# USB.net
KiCad netlist of a schematic drawn in Altium Designer
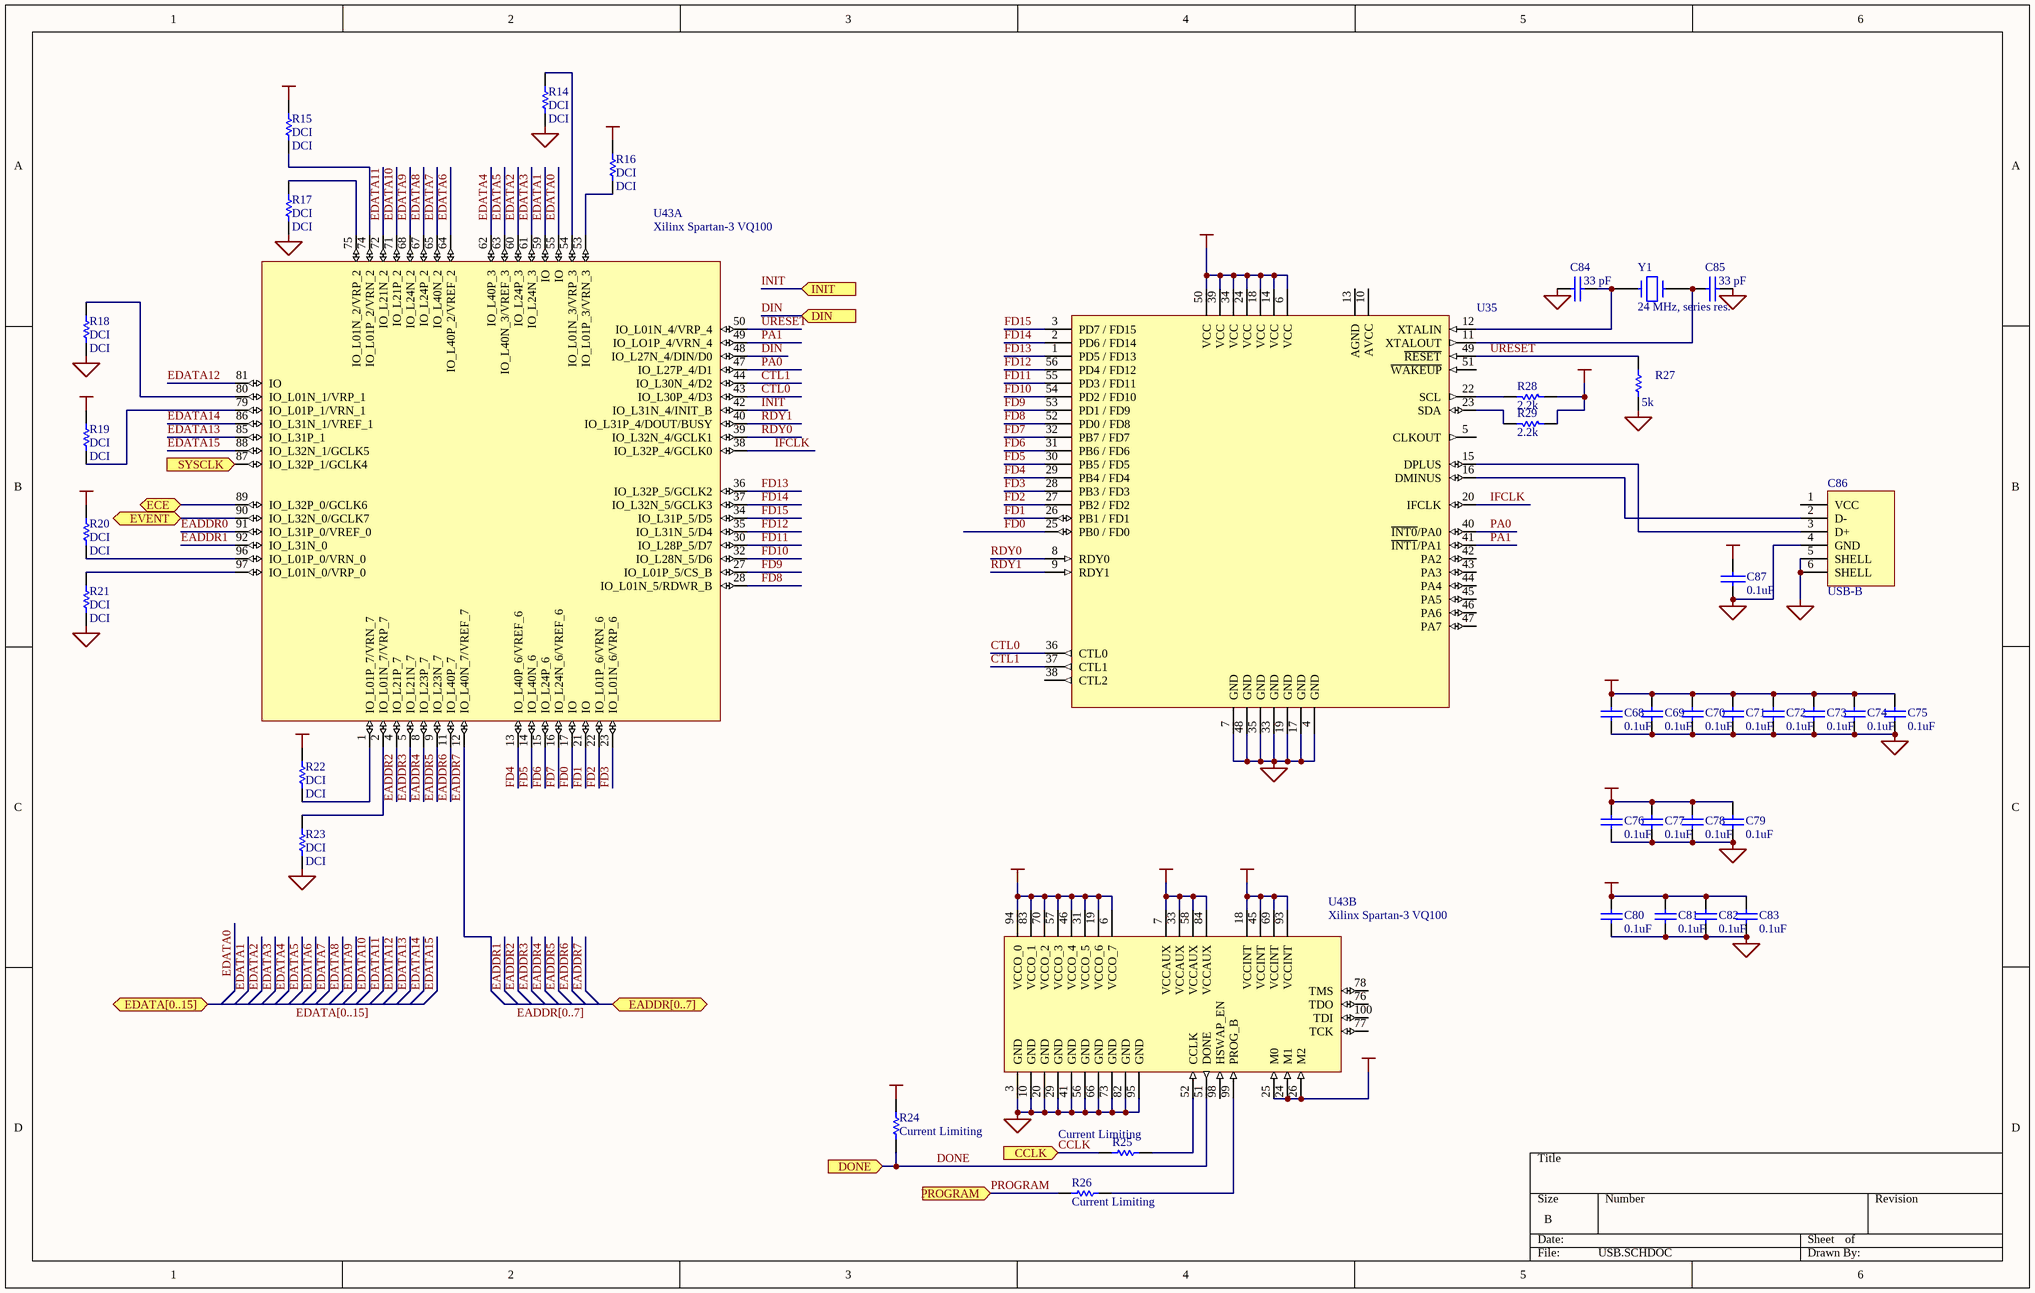
[diagram p0: USB.SCHDOC]

(export (version "E")
  (design (tool "Eeschema 10.0.6"))
  (components
    (comp (ref "C68")
      (value "0.1uF")
      (footprint "CC1608-0603")
      (description "Capacitor")
      (fields
        (field (name "MANUFACTURER") "Generic Components")
        (field (name "Comment") "Cap")
        (field (name "PUBLISHER") "Altium Limited")
      )
      (libsource (lib "Miscellaneous Devices") (part "Cap"))
    )
    (comp (ref "C69")
      (value "0.1uF")
      (footprint "CC1608-0603")
      (description "Capacitor")
      (fields
        (field (name "MANUFACTURER") "Generic Components")
        (field (name "Comment") "Cap")
        (field (name "PUBLISHER") "Altium Limited")
      )
      (libsource (lib "Miscellaneous Devices") (part "Cap"))
    )
    (comp (ref "C70")
      (value "0.1uF")
      (footprint "CC1608-0603")
      (description "Capacitor")
      (fields
        (field (name "MANUFACTURER") "Generic Components")
        (field (name "Comment") "Cap")
        (field (name "PUBLISHER") "Altium Limited")
      )
      (libsource (lib "Miscellaneous Devices") (part "Cap"))
    )
    (comp (ref "C71")
      (value "0.1uF")
      (footprint "CC1608-0603")
      (description "Capacitor")
      (fields
        (field (name "MANUFACTURER") "Generic Components")
        (field (name "Comment") "Cap")
        (field (name "PUBLISHER") "Altium Limited")
      )
      (libsource (lib "Miscellaneous Devices") (part "Cap"))
    )
    (comp (ref "C72")
      (value "0.1uF")
      (footprint "CC1608-0603")
      (description "Capacitor")
      (fields
        (field (name "MANUFACTURER") "Generic Components")
        (field (name "Comment") "Cap")
        (field (name "PUBLISHER") "Altium Limited")
      )
      (libsource (lib "Miscellaneous Devices") (part "Cap"))
    )
    (comp (ref "C73")
      (value "0.1uF")
      (footprint "CC1608-0603")
      (description "Capacitor")
      (fields
        (field (name "MANUFACTURER") "Generic Components")
        (field (name "Comment") "Cap")
        (field (name "PUBLISHER") "Altium Limited")
      )
      (libsource (lib "Miscellaneous Devices") (part "Cap"))
    )
    (comp (ref "C74")
      (value "0.1uF")
      (footprint "CC1608-0603")
      (description "Capacitor")
      (fields
        (field (name "MANUFACTURER") "Generic Components")
        (field (name "Comment") "Cap")
        (field (name "PUBLISHER") "Altium Limited")
      )
      (libsource (lib "Miscellaneous Devices") (part "Cap"))
    )
    (comp (ref "C75")
      (value "0.1uF")
      (footprint "CC1608-0603")
      (description "Capacitor")
      (fields
        (field (name "MANUFACTURER") "Generic Components")
        (field (name "Comment") "Cap")
        (field (name "PUBLISHER") "Altium Limited")
      )
      (libsource (lib "Miscellaneous Devices") (part "Cap"))
    )
    (comp (ref "C76")
      (value "0.1uF")
      (footprint "CC1608-0603")
      (description "Capacitor")
      (fields
        (field (name "MANUFACTURER") "Generic Components")
        (field (name "Comment") "Cap")
        (field (name "PUBLISHER") "Altium Limited")
      )
      (libsource (lib "Miscellaneous Devices") (part "Cap"))
    )
    (comp (ref "C77")
      (value "0.1uF")
      (footprint "CC1608-0603")
      (description "Capacitor")
      (fields
        (field (name "MANUFACTURER") "Generic Components")
        (field (name "Comment") "Cap")
        (field (name "PUBLISHER") "Altium Limited")
      )
      (libsource (lib "Miscellaneous Devices") (part "Cap"))
    )
    (comp (ref "C78")
      (value "0.1uF")
      (footprint "CC1608-0603")
      (description "Capacitor")
      (fields
        (field (name "MANUFACTURER") "Generic Components")
        (field (name "Comment") "Cap")
        (field (name "PUBLISHER") "Altium Limited")
      )
      (libsource (lib "Miscellaneous Devices") (part "Cap"))
    )
    (comp (ref "C79")
      (value "0.1uF")
      (footprint "CC1608-0603")
      (description "Capacitor")
      (fields
        (field (name "MANUFACTURER") "Generic Components")
        (field (name "Comment") "Cap")
        (field (name "PUBLISHER") "Altium Limited")
      )
      (libsource (lib "Miscellaneous Devices") (part "Cap"))
    )
    (comp (ref "C80")
      (value "0.1uF")
      (footprint "CC1608-0603")
      (description "Capacitor")
      (fields
        (field (name "MANUFACTURER") "Generic Components")
        (field (name "Comment") "Cap")
        (field (name "PUBLISHER") "Altium Limited")
      )
      (libsource (lib "Miscellaneous Devices") (part "Cap"))
    )
    (comp (ref "C81")
      (value "0.1uF")
      (footprint "CC1608-0603")
      (description "Capacitor")
      (fields
        (field (name "MANUFACTURER") "Generic Components")
        (field (name "Comment") "Cap")
        (field (name "PUBLISHER") "Altium Limited")
      )
      (libsource (lib "Miscellaneous Devices") (part "Cap"))
    )
    (comp (ref "C82")
      (value "0.1uF")
      (footprint "CC1608-0603")
      (description "Capacitor")
      (fields
        (field (name "MANUFACTURER") "Generic Components")
        (field (name "Comment") "Cap")
        (field (name "PUBLISHER") "Altium Limited")
      )
      (libsource (lib "Miscellaneous Devices") (part "Cap"))
    )
    (comp (ref "C83")
      (value "0.1uF")
      (footprint "CC1608-0603")
      (description "Capacitor")
      (fields
        (field (name "MANUFACTURER") "Generic Components")
        (field (name "Comment") "Cap")
        (field (name "PUBLISHER") "Altium Limited")
      )
      (libsource (lib "Miscellaneous Devices") (part "Cap"))
    )
    (comp (ref "C84")
      (value "33 pF")
      (footprint "CC1608-0603")
      (description "Capacitor")
      (libsource (lib "*") (part "CAP"))
    )
    (comp (ref "C85")
      (value "33 pF")
      (footprint "CC1608-0603")
      (description "Capacitor")
      (libsource (lib "*") (part "CAP"))
    )
    (comp (ref "C86") (value "USB-B") (footprint "USB-B") (libsource (lib "*") (part "USB-B")))
    (comp (ref "C87")
      (value "0.1uF")
      (footprint "CC1608-0603")
      (description "Capacitor")
      (libsource (lib "*") (part "CAP"))
    )
    (comp (ref "R14")
      (value "DCI")
      (footprint "CC1608-0603")
      (description "Resistor")
      (fields
        (field (name "MANUFACTURER") "Generic Components")
        (field (name "ALTIUM_VALUE") "DCI")
        (field (name "PUBLISHER") "Altium Limited")
      )
      (libsource (lib "Miscellaneous Devices") (part "Res1"))
    )
    (comp (ref "R15")
      (value "DCI")
      (footprint "CC1608-0603")
      (description "Resistor")
      (fields
        (field (name "MANUFACTURER") "Generic Components")
        (field (name "ALTIUM_VALUE") "DCI")
        (field (name "PUBLISHER") "Altium Limited")
      )
      (libsource (lib "Miscellaneous Devices") (part "Res1"))
    )
    (comp (ref "R16")
      (value "DCI")
      (footprint "CC1608-0603")
      (description "Resistor")
      (fields
        (field (name "MANUFACTURER") "Generic Components")
        (field (name "ALTIUM_VALUE") "DCI")
        (field (name "PUBLISHER") "Altium Limited")
      )
      (libsource (lib "Miscellaneous Devices") (part "Res1"))
    )
    (comp (ref "R17")
      (value "DCI")
      (footprint "CC1608-0603")
      (description "Resistor")
      (fields
        (field (name "MANUFACTURER") "Generic Components")
        (field (name "ALTIUM_VALUE") "DCI")
        (field (name "PUBLISHER") "Altium Limited")
      )
      (libsource (lib "Miscellaneous Devices") (part "Res1"))
    )
    (comp (ref "R18")
      (value "DCI")
      (footprint "CC1608-0603")
      (description "Resistor")
      (fields
        (field (name "MANUFACTURER") "Generic Components")
        (field (name "ALTIUM_VALUE") "DCI")
        (field (name "PUBLISHER") "Altium Limited")
      )
      (libsource (lib "Miscellaneous Devices") (part "Res1"))
    )
    (comp (ref "R19")
      (value "DCI")
      (footprint "CC1608-0603")
      (description "Resistor")
      (fields
        (field (name "MANUFACTURER") "Generic Components")
        (field (name "ALTIUM_VALUE") "DCI")
        (field (name "PUBLISHER") "Altium Limited")
      )
      (libsource (lib "Miscellaneous Devices") (part "Res1"))
    )
    (comp (ref "R20")
      (value "DCI")
      (footprint "CC1608-0603")
      (description "Resistor")
      (fields
        (field (name "MANUFACTURER") "Generic Components")
        (field (name "ALTIUM_VALUE") "DCI")
        (field (name "PUBLISHER") "Altium Limited")
      )
      (libsource (lib "Miscellaneous Devices") (part "Res1"))
    )
    (comp (ref "R21")
      (value "DCI")
      (footprint "CC1608-0603")
      (description "Resistor")
      (fields
        (field (name "MANUFACTURER") "Generic Components")
        (field (name "ALTIUM_VALUE") "DCI")
        (field (name "PUBLISHER") "Altium Limited")
      )
      (libsource (lib "Miscellaneous Devices") (part "Res1"))
    )
    (comp (ref "R22")
      (value "DCI")
      (footprint "CC1608-0603")
      (description "Resistor")
      (fields
        (field (name "MANUFACTURER") "Generic Components")
        (field (name "ALTIUM_VALUE") "DCI")
        (field (name "PUBLISHER") "Altium Limited")
      )
      (libsource (lib "Miscellaneous Devices") (part "Res1"))
    )
    (comp (ref "R23")
      (value "DCI")
      (footprint "CC1608-0603")
      (description "Resistor")
      (fields
        (field (name "MANUFACTURER") "Generic Components")
        (field (name "ALTIUM_VALUE") "DCI")
        (field (name "PUBLISHER") "Altium Limited")
      )
      (libsource (lib "Miscellaneous Devices") (part "Res1"))
    )
    (comp (ref "R24")
      (value "Current Limiting")
      (footprint "CC1608-0603")
      (description "Resistor")
      (fields (field (name "MANUFACTURER") "Generic Components") (field (name "PUBLISHER") "Altium Limited"))
      (libsource (lib "Miscellaneous Devices") (part "Res1"))
    )
    (comp (ref "R25")
      (value "Current Limiting")
      (footprint "CC1608-0603")
      (description "Resistor")
      (fields (field (name "MANUFACTURER") "Generic Components") (field (name "PUBLISHER") "Altium Limited"))
      (libsource (lib "Miscellaneous Devices") (part "Res1"))
    )
    (comp (ref "R26")
      (value "Current Limiting")
      (footprint "CC1608-0603")
      (description "Resistor")
      (fields (field (name "MANUFACTURER") "Generic Components") (field (name "PUBLISHER") "Altium Limited"))
      (libsource (lib "Miscellaneous Devices") (part "Res1"))
    )
    (comp (ref "R27")
      (value "5k")
      (footprint "CC3216-1206")
      (description "Resistor")
      (fields
        (field (name "MANUFACTURER") "Generic Components")
        (field (name "Comment") "Res1")
        (field (name "PUBLISHER") "Altium Limited")
      )
      (libsource (lib "Miscellaneous Devices") (part "Res1"))
    )
    (comp (ref "R28")
      (value "2.2k")
      (footprint "CC3216-1206")
      (description "Resistor")
      (fields
        (field (name "MANUFACTURER") "Generic Components")
        (field (name "Comment") "Res1")
        (field (name "PUBLISHER") "Altium Limited")
      )
      (libsource (lib "Miscellaneous Devices") (part "Res1"))
    )
    (comp (ref "R29")
      (value "2.2k")
      (footprint "CC3216-1206")
      (description "Resistor")
      (fields
        (field (name "MANUFACTURER") "Generic Components")
        (field (name "Comment") "Res1")
        (field (name "PUBLISHER") "Altium Limited")
      )
      (libsource (lib "Miscellaneous Devices") (part "Res1"))
    )
    (comp (ref "U35")
      (value "~")
      (footprint "SOP56FX2")
      (description "Cypress EZ-USB FX2")
      (libsource (lib "My devices") (part "CY7C68013-56"))
    )
    (comp (ref "U43")
      (value "Xilinx Spartan-3 VQ100")
      (footprint "F-QFP14X14-G100/N")
      (libsource (lib "My devices") (part "XC3S50-VQ100"))
    )
    (comp (ref "Y1")
      (value "24 MHz, series res.")
      (footprint "ECX-3S")
      (description "Crystal")
      (libsource (lib "*") (part "CRYSTAL"))
    )
  )
  (nets
    (net (code "1") (name "+1.2VCCUSB") (class "Default")
      (node (ref "C76") (pin "1") (pinfunction "1_1") (pintype "passive"))
      (node (ref "C77") (pin "1") (pinfunction "1_1") (pintype "passive"))
      (node (ref "C78") (pin "1") (pinfunction "1_1") (pintype "passive"))
      (node (ref "C79") (pin "1") (pinfunction "1_1") (pintype "passive"))
      (node (ref "U43") (pin "18") (pinfunction "VCCINT_18") (pintype "power_in"))
      (node (ref "U43") (pin "45") (pinfunction "VCCINT_45") (pintype "power_in"))
      (node (ref "U43") (pin "69") (pinfunction "VCCINT_69") (pintype "power_in"))
      (node (ref "U43") (pin "93") (pinfunction "VCCINT_93") (pintype "power_in"))
    )
    (net (code "2") (name "+2.5VCC") (class "Default")
      (node (ref "C80") (pin "1") (pinfunction "1_1") (pintype "passive"))
      (node (ref "C81") (pin "1") (pinfunction "1_1") (pintype "passive"))
      (node (ref "C82") (pin "1") (pinfunction "1_1") (pintype "passive"))
      (node (ref "C83") (pin "1") (pinfunction "1_1") (pintype "passive"))
      (node (ref "U43") (pin "33") (pinfunction "VCCAUX_33") (pintype "power_in"))
      (node (ref "U43") (pin "58") (pinfunction "VCCAUX_58") (pintype "power_in"))
      (node (ref "U43") (pin "7") (pinfunction "VCCAUX_7") (pintype "power_in"))
      (node (ref "U43") (pin "84") (pinfunction "VCCAUX_84") (pintype "power_in"))
    )
    (net (code "3") (name "/CCLK") (class "Default")
      (node (ref "R25") (pin "1") (pinfunction "1_1") (pintype "passive"))
    )
    (net (code "4") (name "/CTL0") (class "Default")
      (node (ref "U35") (pin "36") (pinfunction "CTL0_36") (pintype "output"))
      (node (ref "U43") (pin "43") (pinfunction "IO_L30P_4/D3_43") (pintype "bidirectional"))
    )
    (net (code "5") (name "/CTL1") (class "Default")
      (node (ref "U35") (pin "37") (pinfunction "CTL1_37") (pintype "output"))
      (node (ref "U43") (pin "44") (pinfunction "IO_L30N_4/D2_44") (pintype "bidirectional"))
    )
    (net (code "6") (name "/DIN") (class "Default")
      (node (ref "U43") (pin "48") (pinfunction "IO_L27N_4/DIN/D0_48") (pintype "bidirectional"))
    )
    (net (code "7") (name "/DONE") (class "Default")
      (node (ref "R24") (pin "1") (pinfunction "1_1") (pintype "passive"))
      (node (ref "U43") (pin "51") (pinfunction "DONE_51") (pintype "output"))
    )
    (net (code "8") (name "/EADDR0") (class "Default")
      (node (ref "U43") (pin "91") (pinfunction "IO_L31P_0/VREF_0_91") (pintype "bidirectional"))
    )
    (net (code "9") (name "/EADDR1") (class "Default")
      (node (ref "U43") (pin "92") (pinfunction "IO_L31N_0_92") (pintype "bidirectional"))
    )
    (net (code "10") (name "/EADDR2") (class "Default")
      (node (ref "U43") (pin "4") (pinfunction "IO_L21P_7_4") (pintype "bidirectional"))
    )
    (net (code "11") (name "/EADDR3") (class "Default")
      (node (ref "U43") (pin "5") (pinfunction "IO_L21N_7_5") (pintype "bidirectional"))
    )
    (net (code "12") (name "/EADDR4") (class "Default")
      (node (ref "U43") (pin "8") (pinfunction "IO_L23P_7_8") (pintype "bidirectional"))
    )
    (net (code "13") (name "/EADDR5") (class "Default")
      (node (ref "U43") (pin "9") (pinfunction "IO_L23N_7_9") (pintype "bidirectional"))
    )
    (net (code "14") (name "/EADDR6") (class "Default")
      (node (ref "U43") (pin "11") (pinfunction "IO_L40P_7_11") (pintype "bidirectional"))
    )
    (net (code "15") (name "/EADDR7") (class "Default")
      (node (ref "U43") (pin "12") (pinfunction "IO_L40N_7/VREF_7_12") (pintype "bidirectional"))
    )
    (net (code "17") (name "/ECE") (class "Default")
      (node (ref "U43") (pin "89") (pinfunction "IO_L32P_0/GCLK6_89") (pintype "bidirectional"))
    )
    (net (code "18") (name "/EDATA0") (class "Default")
      (node (ref "U43") (pin "55") (pinfunction "IO_55") (pintype "bidirectional"))
    )
    (net (code "19") (name "/EDATA1") (class "Default")
      (node (ref "U43") (pin "59") (pinfunction "IO_59") (pintype "bidirectional"))
    )
    (net (code "20") (name "/EDATA2") (class "Default")
      (node (ref "U43") (pin "60") (pinfunction "IO_L24P_3_60") (pintype "bidirectional"))
    )
    (net (code "21") (name "/EDATA3") (class "Default")
      (node (ref "U43") (pin "61") (pinfunction "IO_L24N_3_61") (pintype "bidirectional"))
    )
    (net (code "22") (name "/EDATA4") (class "Default")
      (node (ref "U43") (pin "62") (pinfunction "IO_L40P_3_62") (pintype "bidirectional"))
    )
    (net (code "23") (name "/EDATA5") (class "Default")
      (node (ref "U43") (pin "63") (pinfunction "IO_L40N_3/VREF_3_63") (pintype "bidirectional"))
    )
    (net (code "24") (name "/EDATA6") (class "Default")
      (node (ref "U43") (pin "64") (pinfunction "IO_L40P_2/VREF_2_64") (pintype "bidirectional"))
    )
    (net (code "25") (name "/EDATA7") (class "Default")
      (node (ref "U43") (pin "65") (pinfunction "IO_L40N_2_65") (pintype "bidirectional"))
    )
    (net (code "26") (name "/EDATA8") (class "Default")
      (node (ref "U43") (pin "67") (pinfunction "IO_L24P_2_67") (pintype "bidirectional"))
    )
    (net (code "27") (name "/EDATA9") (class "Default")
      (node (ref "U43") (pin "68") (pinfunction "IO_L24N_2_68") (pintype "bidirectional"))
    )
    (net (code "28") (name "/EDATA10") (class "Default")
      (node (ref "U43") (pin "71") (pinfunction "IO_L21P_2_71") (pintype "bidirectional"))
    )
    (net (code "29") (name "/EDATA11") (class "Default")
      (node (ref "U43") (pin "72") (pinfunction "IO_L21N_2_72") (pintype "bidirectional"))
    )
    (net (code "30") (name "/EDATA12") (class "Default")
      (node (ref "U43") (pin "81") (pinfunction "IO_81") (pintype "bidirectional"))
    )
    (net (code "31") (name "/EDATA13") (class "Default")
      (node (ref "U43") (pin "85") (pinfunction "IO_L31P_1_85") (pintype "bidirectional"))
    )
    (net (code "32") (name "/EDATA14") (class "Default")
      (node (ref "U43") (pin "86") (pinfunction "IO_L31N_1/VREF_1_86") (pintype "bidirectional"))
    )
    (net (code "33") (name "/EDATA15") (class "Default")
      (node (ref "U43") (pin "88") (pinfunction "IO_L32N_1/GCLK5_88") (pintype "bidirectional"))
    )
    (net (code "35") (name "/EVENT") (class "Default")
      (node (ref "U43") (pin "90") (pinfunction "IO_L32N_0/GCLK7_90") (pintype "bidirectional"))
    )
    (net (code "36") (name "/FD0") (class "Default")
      (node (ref "U35") (pin "25") (pinfunction "PB0_/_FD0_25") (pintype "bidirectional"))
      (node (ref "U43") (pin "17") (pinfunction "IO_17") (pintype "bidirectional"))
    )
    (net (code "37") (name "/FD1") (class "Default")
      (node (ref "U35") (pin "26") (pinfunction "PB1_/_FD1_26") (pintype "bidirectional"))
      (node (ref "U43") (pin "21") (pinfunction "IO_21") (pintype "bidirectional"))
    )
    (net (code "38") (name "/FD2") (class "Default")
      (node (ref "U35") (pin "27") (pinfunction "PB2_/_FD2_27") (pintype "passive"))
      (node (ref "U43") (pin "22") (pinfunction "IO_L01P_6/VRN_6_22") (pintype "bidirectional"))
    )
    (net (code "39") (name "/FD3") (class "Default")
      (node (ref "U35") (pin "28") (pinfunction "PB3_/_FD3_28") (pintype "passive"))
      (node (ref "U43") (pin "23") (pinfunction "IO_L01N_6/VRP_6_23") (pintype "bidirectional"))
    )
    (net (code "40") (name "/FD4") (class "Default")
      (node (ref "U35") (pin "29") (pinfunction "PB4_/_FD4_29") (pintype "passive"))
      (node (ref "U43") (pin "13") (pinfunction "IO_L40P_6/VREF_6_13") (pintype "bidirectional"))
    )
    (net (code "41") (name "/FD5") (class "Default")
      (node (ref "U35") (pin "30") (pinfunction "PB5_/_FD5_30") (pintype "passive"))
      (node (ref "U43") (pin "14") (pinfunction "IO_L40N_6_14") (pintype "bidirectional"))
    )
    (net (code "42") (name "/FD6") (class "Default")
      (node (ref "U35") (pin "31") (pinfunction "PB6_/_FD6_31") (pintype "passive"))
      (node (ref "U43") (pin "15") (pinfunction "IO_L24P_6_15") (pintype "bidirectional"))
    )
    (net (code "43") (name "/FD7") (class "Default")
      (node (ref "U35") (pin "32") (pinfunction "PB7_/_FD7_32") (pintype "passive"))
      (node (ref "U43") (pin "16") (pinfunction "IO_L24N_6/VREF_6_16") (pintype "bidirectional"))
    )
    (net (code "44") (name "/FD8") (class "Default")
      (node (ref "U35") (pin "52") (pinfunction "PD0_/_FD8_52") (pintype "passive"))
      (node (ref "U43") (pin "28") (pinfunction "IO_L01N_5/RDWR_B_28") (pintype "bidirectional"))
    )
    (net (code "45") (name "/FD9") (class "Default")
      (node (ref "U35") (pin "53") (pinfunction "PD1_/_FD9_53") (pintype "passive"))
      (node (ref "U43") (pin "27") (pinfunction "IO_L01P_5/CS_B_27") (pintype "bidirectional"))
    )
    (net (code "46") (name "/FD10") (class "Default")
      (node (ref "U35") (pin "54") (pinfunction "PD2_/_FD10_54") (pintype "passive"))
      (node (ref "U43") (pin "32") (pinfunction "IO_L28N_5/D6_32") (pintype "bidirectional"))
    )
    (net (code "47") (name "/FD11") (class "Default")
      (node (ref "U35") (pin "55") (pinfunction "PD3_/_FD11_55") (pintype "passive"))
      (node (ref "U43") (pin "30") (pinfunction "IO_L28P_5/D7_30") (pintype "bidirectional"))
    )
    (net (code "48") (name "/FD12") (class "Default")
      (node (ref "U35") (pin "56") (pinfunction "PD4_/_FD12_56") (pintype "passive"))
      (node (ref "U43") (pin "35") (pinfunction "IO_L31N_5/D4_35") (pintype "bidirectional"))
    )
    (net (code "49") (name "/FD13") (class "Default")
      (node (ref "U35") (pin "1") (pinfunction "PD5_/_FD13_1") (pintype "passive"))
      (node (ref "U43") (pin "36") (pinfunction "IO_L32P_5/GCLK2_36") (pintype "bidirectional"))
    )
    (net (code "50") (name "/FD14") (class "Default")
      (node (ref "U35") (pin "2") (pinfunction "PD6_/_FD14_2") (pintype "passive"))
      (node (ref "U43") (pin "37") (pinfunction "IO_L32N_5/GCLK3_37") (pintype "bidirectional"))
    )
    (net (code "51") (name "/FD15") (class "Default")
      (node (ref "U35") (pin "3") (pinfunction "PD7_/_FD15_3") (pintype "passive"))
      (node (ref "U43") (pin "34") (pinfunction "IO_L31P_5/D5_34") (pintype "bidirectional"))
    )
    (net (code "52") (name "/IFCLK") (class "Default")
      (node (ref "U35") (pin "20") (pinfunction "IFCLK_20") (pintype "bidirectional"))
      (node (ref "U43") (pin "38") (pinfunction "IO_L32P_4/GCLK0_38") (pintype "bidirectional"))
    )
    (net (code "53") (name "/INIT") (class "Default")
      (node (ref "U43") (pin "42") (pinfunction "IO_L31N_4/INIT_B_42") (pintype "bidirectional"))
    )
    (net (code "54") (name "/PA0") (class "Default")
      (node (ref "U35") (pin "40") (pinfunction "~{INT0}/PA0_40") (pintype "bidirectional"))
      (node (ref "U43") (pin "47") (pinfunction "IO_L27P_4/D1_47") (pintype "bidirectional"))
    )
    (net (code "55") (name "/PA1") (class "Default")
      (node (ref "U35") (pin "41") (pinfunction "~{INT1}/PA1_41") (pintype "bidirectional"))
      (node (ref "U43") (pin "49") (pinfunction "IO_LO1P_4/VRN_4_49") (pintype "bidirectional"))
    )
    (net (code "56") (name "/PROGRAM") (class "Default")
      (node (ref "R26") (pin "1") (pinfunction "1_1") (pintype "passive"))
    )
    (net (code "57") (name "/RDY0") (class "Default")
      (node (ref "U35") (pin "8") (pinfunction "RDY0_8") (pintype "input"))
      (node (ref "U43") (pin "39") (pinfunction "IO_L32N_4/GCLK1_39") (pintype "bidirectional"))
    )
    (net (code "58") (name "/RDY1") (class "Default")
      (node (ref "U35") (pin "9") (pinfunction "RDY1_9") (pintype "input"))
      (node (ref "U43") (pin "40") (pinfunction "IO_L31P_4/DOUT/BUSY_40") (pintype "bidirectional"))
    )
    (net (code "59") (name "/SYSCLK") (class "Default")
      (node (ref "U43") (pin "87") (pinfunction "IO_L32P_1/GCLK4_87") (pintype "bidirectional"))
    )
    (net (code "60") (name "/URESET") (class "Default")
      (node (ref "R27") (pin "2") (pinfunction "2_2") (pintype "passive"))
      (node (ref "U35") (pin "49") (pinfunction "~{RESET}_49") (pintype "input"))
      (node (ref "U43") (pin "50") (pinfunction "IO_L01N_4/VRP_4_50") (pintype "bidirectional"))
    )
    (net (code "61") (name "GND") (class "Default")
      (node (ref "C68") (pin "2") (pinfunction "2_2") (pintype "passive"))
      (node (ref "C69") (pin "2") (pinfunction "2_2") (pintype "passive"))
      (node (ref "C70") (pin "2") (pinfunction "2_2") (pintype "passive"))
      (node (ref "C71") (pin "2") (pinfunction "2_2") (pintype "passive"))
      (node (ref "C72") (pin "2") (pinfunction "2_2") (pintype "passive"))
      (node (ref "C73") (pin "2") (pinfunction "2_2") (pintype "passive"))
      (node (ref "C74") (pin "2") (pinfunction "2_2") (pintype "passive"))
      (node (ref "C75") (pin "2") (pinfunction "2_2") (pintype "passive"))
      (node (ref "C76") (pin "2") (pinfunction "2_2") (pintype "passive"))
      (node (ref "C77") (pin "2") (pinfunction "2_2") (pintype "passive"))
      (node (ref "C78") (pin "2") (pinfunction "2_2") (pintype "passive"))
      (node (ref "C79") (pin "2") (pinfunction "2_2") (pintype "passive"))
      (node (ref "C80") (pin "2") (pinfunction "2_2") (pintype "passive"))
      (node (ref "C81") (pin "2") (pinfunction "2_2") (pintype "passive"))
      (node (ref "C82") (pin "2") (pinfunction "2_2") (pintype "passive"))
      (node (ref "C83") (pin "2") (pinfunction "2_2") (pintype "passive"))
      (node (ref "C84") (pin "2") (pinfunction "2_2") (pintype "passive"))
      (node (ref "C85") (pin "1") (pinfunction "1_1") (pintype "passive"))
      (node (ref "C86") (pin "4") (pinfunction "GND_4") (pintype "passive"))
      (node (ref "C86") (pin "5") (pinfunction "SHELL_5") (pintype "passive"))
      (node (ref "C86") (pin "6") (pinfunction "SHELL_6") (pintype "passive"))
      (node (ref "C87") (pin "2") (pinfunction "2_2") (pintype "passive"))
      (node (ref "R14") (pin "1") (pinfunction "1_1") (pintype "passive"))
      (node (ref "R17") (pin "1") (pinfunction "1_1") (pintype "passive"))
      (node (ref "R18") (pin "1") (pinfunction "1_1") (pintype "passive"))
      (node (ref "R21") (pin "1") (pinfunction "1_1") (pintype "passive"))
      (node (ref "R23") (pin "1") (pinfunction "1_1") (pintype "passive"))
      (node (ref "R27") (pin "1") (pinfunction "1_1") (pintype "passive"))
      (node (ref "U35") (pin "17") (pinfunction "GND_17") (pintype "power_in"))
      (node (ref "U35") (pin "19") (pinfunction "GND_19") (pintype "power_in"))
      (node (ref "U35") (pin "33") (pinfunction "GND_33") (pintype "power_in"))
      (node (ref "U35") (pin "35") (pinfunction "GND_35") (pintype "power_in"))
      (node (ref "U35") (pin "4") (pinfunction "GND_4") (pintype "power_in"))
      (node (ref "U35") (pin "48") (pinfunction "GND_48") (pintype "power_in"))
      (node (ref "U35") (pin "7") (pinfunction "GND_7") (pintype "power_in"))
      (node (ref "U43") (pin "10") (pinfunction "GND_10") (pintype "power_in"))
      (node (ref "U43") (pin "20") (pinfunction "GND_20") (pintype "power_in"))
      (node (ref "U43") (pin "29") (pinfunction "GND_29") (pintype "power_in"))
      (node (ref "U43") (pin "3") (pinfunction "GND_3") (pintype "power_in"))
      (node (ref "U43") (pin "41") (pinfunction "GND_41") (pintype "power_in"))
      (node (ref "U43") (pin "56") (pinfunction "GND_56") (pintype "power_in"))
      (node (ref "U43") (pin "66") (pinfunction "GND_66") (pintype "power_in"))
      (node (ref "U43") (pin "73") (pinfunction "GND_73") (pintype "power_in"))
      (node (ref "U43") (pin "82") (pinfunction "GND_82") (pintype "power_in"))
      (node (ref "U43") (pin "95") (pinfunction "GND_95") (pintype "power_in"))
    )
    (net (code "62") (name "Net-(C86-D+)") (class "Default")
      (node (ref "C86") (pin "3") (pinfunction "D+_3") (pintype "passive"))
      (node (ref "U35") (pin "15") (pinfunction "DPLUS_15") (pintype "bidirectional"))
    )
    (net (code "63") (name "Net-(C86-D-)") (class "Default")
      (node (ref "C86") (pin "2") (pinfunction "D-_2") (pintype "passive"))
      (node (ref "U35") (pin "16") (pinfunction "DMINUS_16") (pintype "bidirectional"))
    )
    (net (code "64") (name "Net-(U35-SCL)") (class "Default")
      (node (ref "R28") (pin "2") (pinfunction "2_2") (pintype "passive"))
      (node (ref "U35") (pin "22") (pinfunction "SCL_22") (pintype "output"))
    )
    (net (code "65") (name "Net-(U35-SDA)") (class "Default")
      (node (ref "R29") (pin "2") (pinfunction "2_2") (pintype "passive"))
      (node (ref "U35") (pin "23") (pinfunction "SDA_23") (pintype "bidirectional"))
    )
    (net (code "66") (name "Net-(U35-XTALIN)") (class "Default")
      (node (ref "C84") (pin "1") (pinfunction "1_1") (pintype "passive"))
      (node (ref "U35") (pin "12") (pinfunction "XTALIN_12") (pintype "input"))
      (node (ref "Y1") (pin "1") (pinfunction "1_1") (pintype "passive"))
    )
    (net (code "67") (name "Net-(U35-XTALOUT)") (class "Default")
      (node (ref "C85") (pin "2") (pinfunction "2_2") (pintype "passive"))
      (node (ref "U35") (pin "11") (pinfunction "XTALOUT_11") (pintype "output"))
      (node (ref "Y1") (pin "2") (pinfunction "2_2") (pintype "passive"))
    )
    (net (code "68") (name "Net-(U43A-IO_L01N_0{slash}VRP_0)") (class "Default")
      (node (ref "R21") (pin "2") (pinfunction "2_2") (pintype "passive"))
      (node (ref "U43") (pin "97") (pinfunction "IO_L01N_0/VRP_0_97") (pintype "bidirectional"))
    )
    (net (code "69") (name "Net-(U43A-IO_L01N_1{slash}VRP_1)") (class "Default")
      (node (ref "R18") (pin "2") (pinfunction "2_2") (pintype "passive"))
      (node (ref "U43") (pin "80") (pinfunction "IO_L01N_1/VRP_1_80") (pintype "bidirectional"))
    )
    (net (code "70") (name "Net-(U43A-IO_L01N_2{slash}VRP_2)") (class "Default")
      (node (ref "R17") (pin "2") (pinfunction "2_2") (pintype "passive"))
      (node (ref "U43") (pin "75") (pinfunction "IO_L01N_2/VRP_2_75") (pintype "bidirectional"))
    )
    (net (code "71") (name "Net-(U43A-IO_L01N_3{slash}VRP_3)") (class "Default")
      (node (ref "R14") (pin "2") (pinfunction "2_2") (pintype "passive"))
      (node (ref "U43") (pin "54") (pinfunction "IO_L01N_3/VRP_3_54") (pintype "bidirectional"))
    )
    (net (code "72") (name "Net-(U43A-IO_L01N_7{slash}VRP_7)") (class "Default")
      (node (ref "R23") (pin "2") (pinfunction "2_2") (pintype "passive"))
      (node (ref "U43") (pin "2") (pinfunction "IO_L01N_7/VRP_7_2") (pintype "bidirectional"))
    )
    (net (code "73") (name "Net-(U43A-IO_L01P_0{slash}VRN_0)") (class "Default")
      (node (ref "R20") (pin "1") (pinfunction "1_1") (pintype "passive"))
      (node (ref "U43") (pin "96") (pinfunction "IO_L01P_0/VRN_0_96") (pintype "bidirectional"))
    )
    (net (code "74") (name "Net-(U43A-IO_L01P_1{slash}VRN_1)") (class "Default")
      (node (ref "R19") (pin "1") (pinfunction "1_1") (pintype "passive"))
      (node (ref "U43") (pin "79") (pinfunction "IO_L01P_1/VRN_1_79") (pintype "bidirectional"))
    )
    (net (code "75") (name "Net-(U43A-IO_L01P_2{slash}VRN_2)") (class "Default")
      (node (ref "R15") (pin "1") (pinfunction "1_1") (pintype "passive"))
      (node (ref "U43") (pin "74") (pinfunction "IO_L01P_2/VRN_2_74") (pintype "bidirectional"))
    )
    (net (code "76") (name "Net-(U43A-IO_L01P_3{slash}VRN_3)") (class "Default")
      (node (ref "R16") (pin "1") (pinfunction "1_1") (pintype "passive"))
      (node (ref "U43") (pin "53") (pinfunction "IO_L01P_3/VRN_3_53") (pintype "bidirectional"))
    )
    (net (code "77") (name "Net-(U43A-IO_L01P_7{slash}VRN_7)") (class "Default")
      (node (ref "R22") (pin "1") (pinfunction "1_1") (pintype "passive"))
      (node (ref "U43") (pin "1") (pinfunction "IO_L01P_7/VRN_7_1") (pintype "bidirectional"))
    )
    (net (code "78") (name "Net-(U43B-CCLK)") (class "Default")
      (node (ref "R25") (pin "2") (pinfunction "2_2") (pintype "passive"))
      (node (ref "U43") (pin "52") (pinfunction "CCLK_52") (pintype "input"))
    )
    (net (code "79") (name "Net-(U43B-PROG_B)") (class "Default")
      (node (ref "R26") (pin "2") (pinfunction "2_2") (pintype "passive"))
      (node (ref "U43") (pin "99") (pinfunction "PROG_B_99") (pintype "input"))
    )
    (net (code "80") (name "VCC") (class "Default")
      (node (ref "C68") (pin "1") (pinfunction "1_1") (pintype "passive"))
      (node (ref "C69") (pin "1") (pinfunction "1_1") (pintype "passive"))
      (node (ref "C70") (pin "1") (pinfunction "1_1") (pintype "passive"))
      (node (ref "C71") (pin "1") (pinfunction "1_1") (pintype "passive"))
      (node (ref "C72") (pin "1") (pinfunction "1_1") (pintype "passive"))
      (node (ref "C73") (pin "1") (pinfunction "1_1") (pintype "passive"))
      (node (ref "C74") (pin "1") (pinfunction "1_1") (pintype "passive"))
      (node (ref "C75") (pin "1") (pinfunction "1_1") (pintype "passive"))
      (node (ref "C87") (pin "1") (pinfunction "1_1") (pintype "passive"))
      (node (ref "R15") (pin "2") (pinfunction "2_2") (pintype "passive"))
      (node (ref "R16") (pin "2") (pinfunction "2_2") (pintype "passive"))
      (node (ref "R19") (pin "2") (pinfunction "2_2") (pintype "passive"))
      (node (ref "R20") (pin "2") (pinfunction "2_2") (pintype "passive"))
      (node (ref "R22") (pin "2") (pinfunction "2_2") (pintype "passive"))
      (node (ref "R24") (pin "2") (pinfunction "2_2") (pintype "passive"))
      (node (ref "R28") (pin "1") (pinfunction "1_1") (pintype "passive"))
      (node (ref "R29") (pin "1") (pinfunction "1_1") (pintype "passive"))
      (node (ref "U35") (pin "14") (pinfunction "VCC_14") (pintype "power_in"))
      (node (ref "U35") (pin "18") (pinfunction "VCC_18") (pintype "power_in"))
      (node (ref "U35") (pin "24") (pinfunction "VCC_24") (pintype "power_in"))
      (node (ref "U35") (pin "34") (pinfunction "VCC_34") (pintype "power_in"))
      (node (ref "U35") (pin "39") (pinfunction "VCC_39") (pintype "power_in"))
      (node (ref "U35") (pin "50") (pinfunction "VCC_50") (pintype "power_in"))
      (node (ref "U35") (pin "6") (pinfunction "VCC_6") (pintype "power_in"))
      (node (ref "U43") (pin "19") (pinfunction "VCCO_6_19") (pintype "power_in"))
      (node (ref "U43") (pin "24") (pinfunction "M1_24") (pintype "input"))
      (node (ref "U43") (pin "25") (pinfunction "M0_25") (pintype "input"))
      (node (ref "U43") (pin "26") (pinfunction "M2_26") (pintype "input"))
      (node (ref "U43") (pin "31") (pinfunction "VCCO_5_31") (pintype "power_in"))
      (node (ref "U43") (pin "46") (pinfunction "VCCO_4_46") (pintype "power_in"))
      (node (ref "U43") (pin "57") (pinfunction "VCCO_3_57") (pintype "power_in"))
      (node (ref "U43") (pin "6") (pinfunction "VCCO_7_6") (pintype "power_in"))
      (node (ref "U43") (pin "70") (pinfunction "VCCO_2_70") (pintype "power_in"))
      (node (ref "U43") (pin "83") (pinfunction "VCCO_1_83") (pintype "power_in"))
      (node (ref "U43") (pin "94") (pinfunction "VCCO_0_94") (pintype "power_in"))
    )
    (net (code "81") (name "unconnected-(C86-VCC-Pad1)") (class "Default")
      (node (ref "C86") (pin "1") (pinfunction "VCC_1") (pintype "passive"))
    )
    (net (code "82") (name "unconnected-(U35-AGND-Pad13)") (class "Default")
      (node (ref "U35") (pin "13") (pinfunction "AGND_13") (pintype "power_in"))
    )
    (net (code "83") (name "unconnected-(U35-AVCC-Pad10)") (class "Default")
      (node (ref "U35") (pin "10") (pinfunction "AVCC_10") (pintype "power_in"))
    )
    (net (code "84") (name "unconnected-(U35-CLKOUT-Pad5)") (class "Default")
      (node (ref "U35") (pin "5") (pinfunction "CLKOUT_5") (pintype "output"))
    )
    (net (code "85") (name "unconnected-(U35-CTL2-Pad38)") (class "Default")
      (node (ref "U35") (pin "38") (pinfunction "CTL2_38") (pintype "output"))
    )
    (net (code "86") (name "unconnected-(U35-PA2-Pad42)") (class "Default")
      (node (ref "U35") (pin "42") (pinfunction "PA2_42") (pintype "bidirectional"))
    )
    (net (code "87") (name "unconnected-(U35-PA3-Pad43)") (class "Default")
      (node (ref "U35") (pin "43") (pinfunction "PA3_43") (pintype "bidirectional"))
    )
    (net (code "88") (name "unconnected-(U35-PA4-Pad44)") (class "Default")
      (node (ref "U35") (pin "44") (pinfunction "PA4_44") (pintype "bidirectional"))
    )
    (net (code "89") (name "unconnected-(U35-PA5-Pad45)") (class "Default")
      (node (ref "U35") (pin "45") (pinfunction "PA5_45") (pintype "bidirectional"))
    )
    (net (code "90") (name "unconnected-(U35-PA6-Pad46)") (class "Default")
      (node (ref "U35") (pin "46") (pinfunction "PA6_46") (pintype "bidirectional"))
    )
    (net (code "91") (name "unconnected-(U35-PA7-Pad47)") (class "Default")
      (node (ref "U35") (pin "47") (pinfunction "PA7_47") (pintype "bidirectional"))
    )
    (net (code "92") (name "unconnected-(U35-~{WAKEUP}-Pad51)") (class "Default")
      (node (ref "U35") (pin "51") (pinfunction "~{WAKEUP}_51") (pintype "input"))
    )
    (net (code "93") (name "unconnected-(U43B-HSWAP_EN-Pad98)") (class "Default")
      (node (ref "U43") (pin "98") (pinfunction "HSWAP_EN_98") (pintype "input"))
    )
    (net (code "94") (name "unconnected-(U43B-TCK-Pad77)") (class "Default")
      (node (ref "U43") (pin "77") (pinfunction "TCK_77") (pintype "bidirectional"))
    )
    (net (code "95") (name "unconnected-(U43B-TDI-Pad100)") (class "Default")
      (node (ref "U43") (pin "100") (pinfunction "TDI_100") (pintype "bidirectional"))
    )
    (net (code "96") (name "unconnected-(U43B-TDO-Pad76)") (class "Default")
      (node (ref "U43") (pin "76") (pinfunction "TDO_76") (pintype "bidirectional"))
    )
    (net (code "97") (name "unconnected-(U43B-TMS-Pad78)") (class "Default")
      (node (ref "U43") (pin "78") (pinfunction "TMS_78") (pintype "bidirectional"))
    )
  )
)
